# SignalSelector.net
KiCad netlist of a schematic drawn in EAGLE
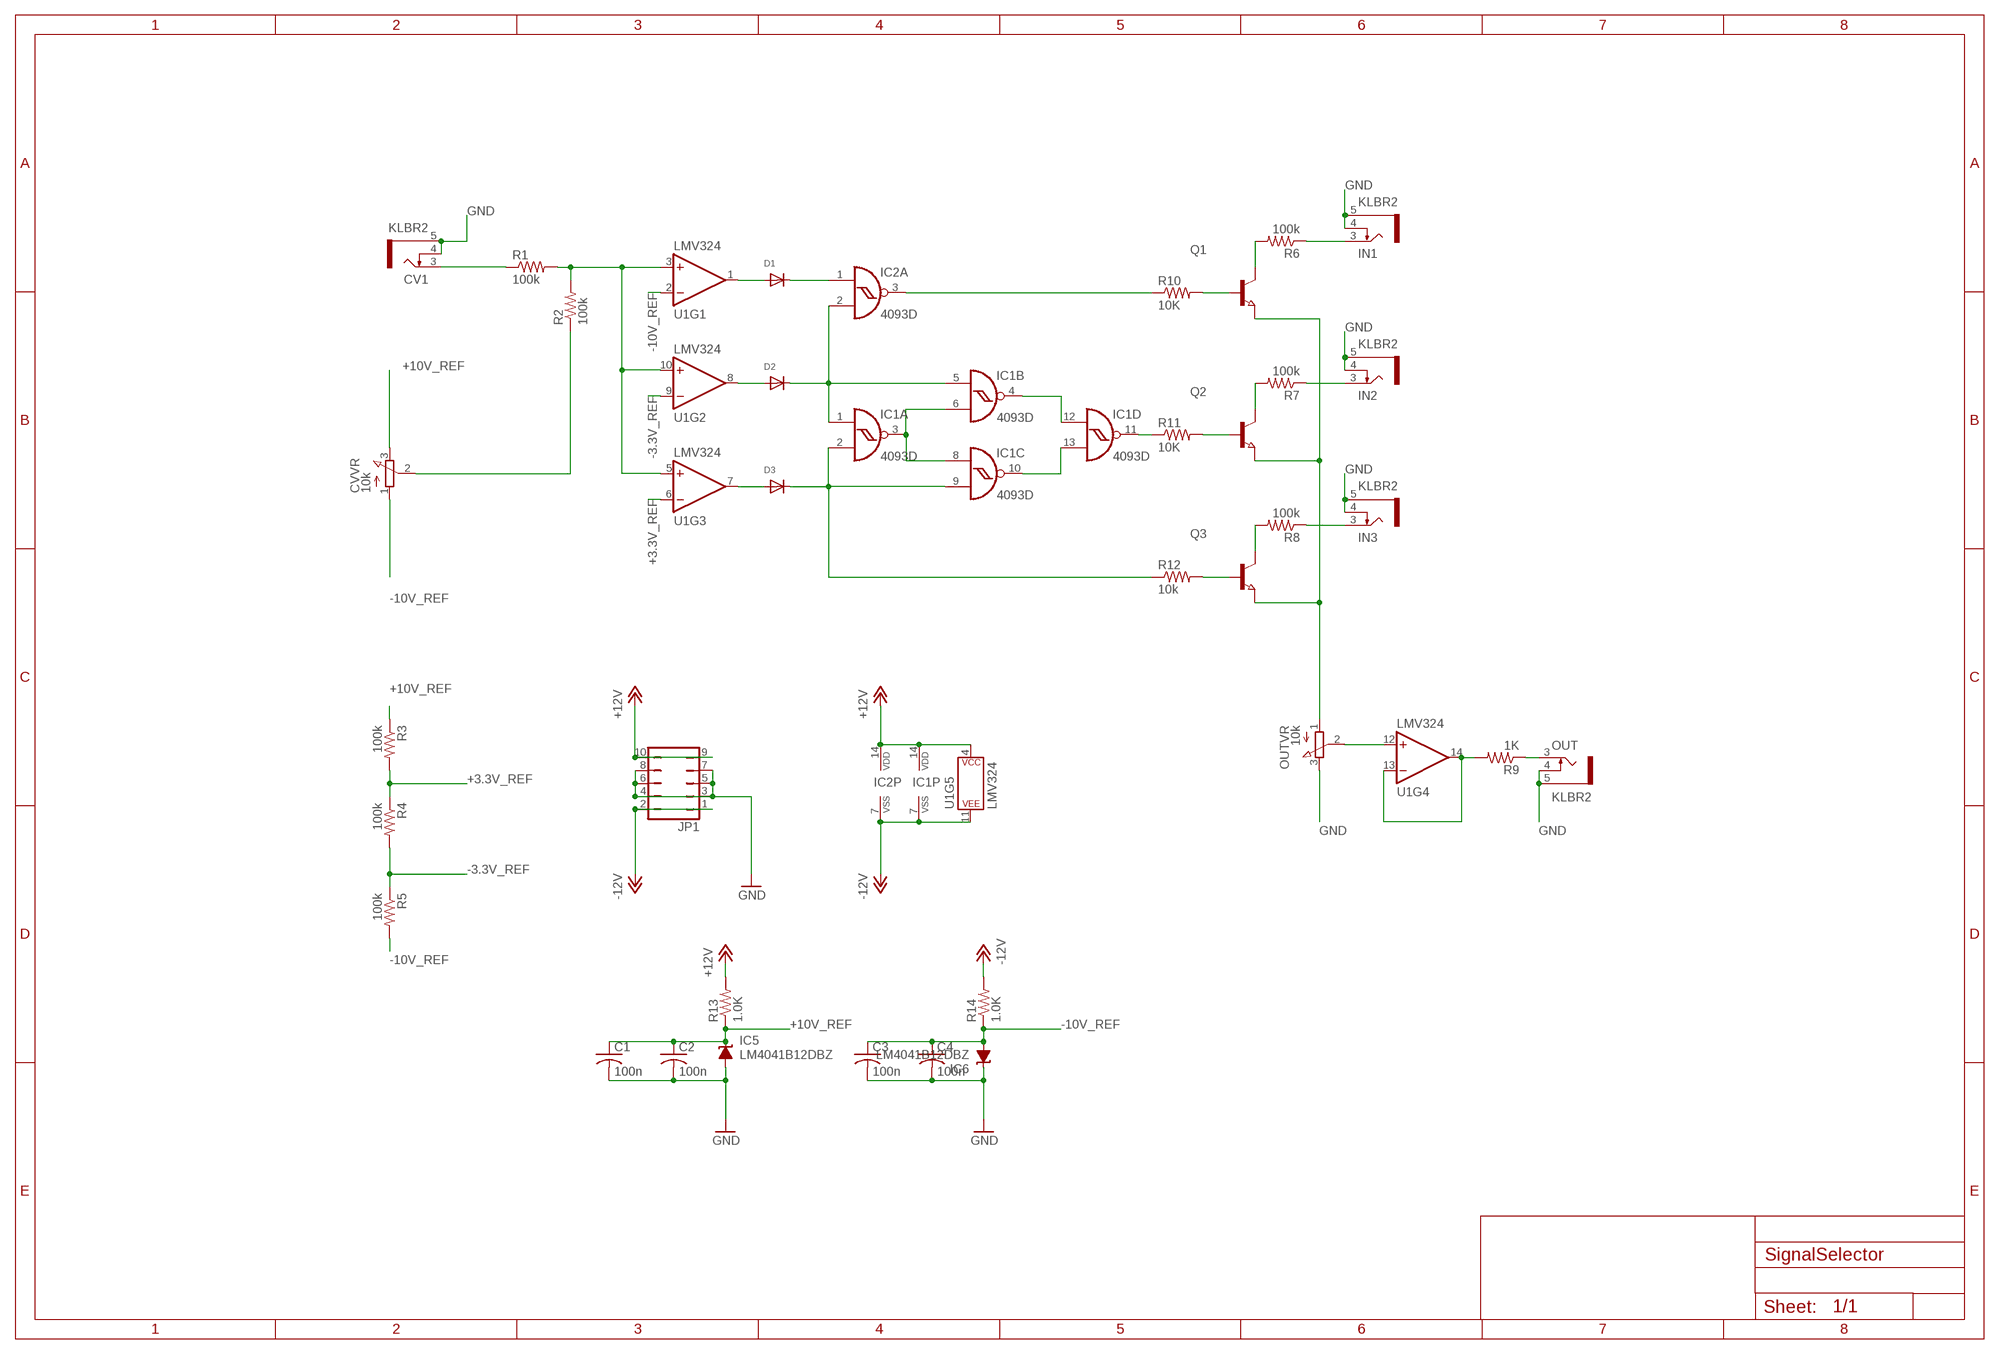
[diagram p0: schematic, sheet 1]

(export (version "E")
  (design (tool "Eeschema 10.0.6"))
  (components
    (comp (ref "C1")
      (value "100n")
      (footprint "eagle-import:C0603")
      (libsource (lib "eagle-import") (part "C-USC0603"))
    )
    (comp (ref "C2")
      (value "100n")
      (footprint "eagle-import:C0603")
      (libsource (lib "eagle-import") (part "C-USC0603"))
    )
    (comp (ref "C3")
      (value "100n")
      (footprint "eagle-import:C0603")
      (libsource (lib "eagle-import") (part "C-USC0603"))
    )
    (comp (ref "C4")
      (value "100n")
      (footprint "eagle-import:C0603")
      (libsource (lib "eagle-import") (part "C-USC0603"))
    )
    (comp (ref "CV1")
      (value "KLBR2")
      (footprint "eagle-import:KLBR2")
      (libsource (lib "eagle-import") (part "KLBR?2"))
    )
    (comp (ref "CVVR")
      (value "10k")
      (footprint "eagle-import:3RP_1610N")
      (libsource (lib "eagle-import") (part "3RP/1610N"))
    )
    (comp (ref "D1")
      (value "DIODE_SOD-123FL")
      (footprint "eagle-import:SOD-123FL")
      (libsource (lib "eagle-import") (part "DIODE_SOD-123FL"))
    )
    (comp (ref "D2")
      (value "DIODE_SOD-123FL")
      (footprint "eagle-import:SOD-123FL")
      (libsource (lib "eagle-import") (part "DIODE_SOD-123FL"))
    )
    (comp (ref "D3")
      (value "DIODE_SOD-123FL")
      (footprint "eagle-import:SOD-123FL")
      (libsource (lib "eagle-import") (part "DIODE_SOD-123FL"))
    )
    (comp (ref "IC1")
      (value "4093D")
      (footprint "eagle-import:SO14")
      (libsource (lib "eagle-import") (part "4093D"))
    )
    (comp (ref "IC2")
      (value "4093D")
      (footprint "eagle-import:SO14")
      (libsource (lib "eagle-import") (part "4093D"))
    )
    (comp (ref "IC5")
      (value "LM4041B12DBZ")
      (footprint "eagle-import:DBZ_R-PDSO-G3")
      (fields (field (name "MPN") "LM4041B12IDBZR"))
      (libsource (lib "eagle-import") (part "LM4041DBZB12"))
    )
    (comp (ref "IC6")
      (value "LM4041B12DBZ")
      (footprint "eagle-import:DBZ_R-PDSO-G3")
      (fields (field (name "MPN") "LM4041B12IDBZR"))
      (libsource (lib "eagle-import") (part "LM4041DBZB12"))
    )
    (comp (ref "IN1")
      (value "KLBR2")
      (footprint "eagle-import:KLBR2")
      (libsource (lib "eagle-import") (part "KLBR?2"))
    )
    (comp (ref "IN2")
      (value "KLBR2")
      (footprint "eagle-import:KLBR2")
      (libsource (lib "eagle-import") (part "KLBR?2"))
    )
    (comp (ref "IN3")
      (value "KLBR2")
      (footprint "eagle-import:KLBR2")
      (libsource (lib "eagle-import") (part "KLBR?2"))
    )
    (comp (ref "JP1")
      (value "JP5Q")
      (footprint "eagle-import:JP5Q")
      (libsource (lib "eagle-import") (part "JP5Q"))
    )
    (comp (ref "OUT")
      (value "KLBR2")
      (footprint "eagle-import:KLBR2")
      (libsource (lib "eagle-import") (part "KLBR?2"))
    )
    (comp (ref "OUTVR")
      (value "10k")
      (footprint "eagle-import:3RP_1610N")
      (libsource (lib "eagle-import") (part "3RP/1610N"))
    )
    (comp (ref "Q1")
      (value "NPN-TRANSISTOR_SOT23")
      (footprint "eagle-import:SOT23")
      (libsource (lib "eagle-import") (part "NPN-TRANSISTOR_SOT23"))
    )
    (comp (ref "Q2")
      (value "NPN-TRANSISTOR_SOT23")
      (footprint "eagle-import:SOT23")
      (libsource (lib "eagle-import") (part "NPN-TRANSISTOR_SOT23"))
    )
    (comp (ref "Q3")
      (value "NPN-TRANSISTOR_SOT23")
      (footprint "eagle-import:SOT23")
      (libsource (lib "eagle-import") (part "NPN-TRANSISTOR_SOT23"))
    )
    (comp (ref "R1")
      (value "100k")
      (footprint "eagle-import:R0603")
      (libsource (lib "eagle-import") (part "R-US_R0603"))
    )
    (comp (ref "R2")
      (value "100k")
      (footprint "eagle-import:R0603")
      (libsource (lib "eagle-import") (part "R-US_R0603"))
    )
    (comp (ref "R3")
      (value "100k")
      (footprint "eagle-import:R0603")
      (libsource (lib "eagle-import") (part "R-US_R0603"))
    )
    (comp (ref "R4")
      (value "100k")
      (footprint "eagle-import:R0603")
      (libsource (lib "eagle-import") (part "R-US_R0603"))
    )
    (comp (ref "R5")
      (value "100k")
      (footprint "eagle-import:R0603")
      (libsource (lib "eagle-import") (part "R-US_R0603"))
    )
    (comp (ref "R6")
      (value "100k")
      (footprint "eagle-import:R0603")
      (libsource (lib "eagle-import") (part "R-US_R0603"))
    )
    (comp (ref "R7")
      (value "100k")
      (footprint "eagle-import:R0603")
      (libsource (lib "eagle-import") (part "R-US_R0603"))
    )
    (comp (ref "R8")
      (value "100k")
      (footprint "eagle-import:R0603")
      (libsource (lib "eagle-import") (part "R-US_R0603"))
    )
    (comp (ref "R9")
      (value "1K")
      (footprint "eagle-import:R0603")
      (libsource (lib "eagle-import") (part "R-US_R0603"))
    )
    (comp (ref "R10")
      (value "10K")
      (footprint "eagle-import:R0603")
      (libsource (lib "eagle-import") (part "R-US_R0603"))
    )
    (comp (ref "R11")
      (value "10K")
      (footprint "eagle-import:R0603")
      (libsource (lib "eagle-import") (part "R-US_R0603"))
    )
    (comp (ref "R12")
      (value "10k")
      (footprint "eagle-import:R0603")
      (libsource (lib "eagle-import") (part "R-US_R0603"))
    )
    (comp (ref "R13")
      (value "1.0K")
      (footprint "eagle-import:R0603")
      (libsource (lib "eagle-import") (part "R-US_R0603"))
    )
    (comp (ref "R14")
      (value "1.0K")
      (footprint "eagle-import:R0603")
      (libsource (lib "eagle-import") (part "R-US_R0603"))
    )
    (comp (ref "U1")
      (value "LMV324")
      (footprint "eagle-import:SO14")
      (libsource (lib "eagle-import") (part "LMV324"))
    )
  )
  (nets
    (net (code "1") (name "+12V") (class "Default")
      (node (ref "IC1") (pin "14") (pinfunction "VDD_14") (pintype "power_in"))
      (node (ref "IC2") (pin "14") (pinfunction "VDD_14") (pintype "power_in"))
      (node (ref "JP1") (pin "10") (pinfunction "10_10") (pintype "passive"))
      (node (ref "JP1") (pin "9") (pinfunction "9_9") (pintype "passive"))
      (node (ref "R13") (pin "2") (pinfunction "2_2") (pintype "passive"))
      (node (ref "U1") (pin "4") (pinfunction "P$V+_4") (pintype "bidirectional"))
    )
    (net (code "2") (name "-12V") (class "Default")
      (node (ref "IC1") (pin "7") (pinfunction "VSS_7") (pintype "power_in"))
      (node (ref "IC2") (pin "7") (pinfunction "VSS_7") (pintype "power_in"))
      (node (ref "JP1") (pin "1") (pinfunction "1_1") (pintype "passive"))
      (node (ref "JP1") (pin "2") (pinfunction "2_2") (pintype "passive"))
      (node (ref "R14") (pin "2") (pinfunction "2_2") (pintype "passive"))
      (node (ref "U1") (pin "11") (pinfunction "P$V-_11") (pintype "bidirectional"))
    )
    (net (code "3") (name "/+3.3V_REF") (class "Default")
      (node (ref "R3") (pin "2") (pinfunction "2_2") (pintype "passive"))
      (node (ref "R4") (pin "1") (pinfunction "1_1") (pintype "passive"))
      (node (ref "U1") (pin "6") (pinfunction "-IN_6") (pintype "input"))
    )
    (net (code "4") (name "/+10V_REF") (class "Default")
      (node (ref "C1") (pin "1") (pinfunction "1_1") (pintype "passive"))
      (node (ref "C2") (pin "1") (pinfunction "1_1") (pintype "passive"))
      (node (ref "CVVR") (pin "3") (pinfunction "E_3") (pintype "passive"))
      (node (ref "IC5") (pin "1") (pinfunction "C_1") (pintype "passive"))
      (node (ref "R13") (pin "1") (pinfunction "1_1") (pintype "passive"))
      (node (ref "R3") (pin "1") (pinfunction "1_1") (pintype "passive"))
    )
    (net (code "5") (name "/-3.3V_REF") (class "Default")
      (node (ref "R4") (pin "2") (pinfunction "2_2") (pintype "passive"))
      (node (ref "R5") (pin "1") (pinfunction "1_1") (pintype "passive"))
      (node (ref "U1") (pin "9") (pinfunction "-IN_9") (pintype "input"))
    )
    (net (code "6") (name "/-10V_REF") (class "Default")
      (node (ref "C3") (pin "1") (pinfunction "1_1") (pintype "passive"))
      (node (ref "C4") (pin "1") (pinfunction "1_1") (pintype "passive"))
      (node (ref "CVVR") (pin "1") (pinfunction "A_1") (pintype "passive"))
      (node (ref "IC6") (pin "2") (pinfunction "A_2") (pintype "passive"))
      (node (ref "R14") (pin "1") (pinfunction "1_1") (pintype "passive"))
      (node (ref "R5") (pin "2") (pinfunction "2_2") (pintype "passive"))
      (node (ref "U1") (pin "2") (pinfunction "-IN_2") (pintype "input"))
    )
    (net (code "7") (name "GND") (class "Default")
      (node (ref "C1") (pin "2") (pinfunction "2_2") (pintype "passive"))
      (node (ref "C2") (pin "2") (pinfunction "2_2") (pintype "passive"))
      (node (ref "C3") (pin "2") (pinfunction "2_2") (pintype "passive"))
      (node (ref "C4") (pin "2") (pinfunction "2_2") (pintype "passive"))
      (node (ref "CV1") (pin "4") (pinfunction "4_4") (pintype "passive"))
      (node (ref "CV1") (pin "5") (pinfunction "5_5") (pintype "passive"))
      (node (ref "IC5") (pin "2") (pinfunction "A_2") (pintype "passive"))
      (node (ref "IC6") (pin "1") (pinfunction "C_1") (pintype "passive"))
      (node (ref "IN1") (pin "4") (pinfunction "4_4") (pintype "passive"))
      (node (ref "IN1") (pin "5") (pinfunction "5_5") (pintype "passive"))
      (node (ref "IN2") (pin "4") (pinfunction "4_4") (pintype "passive"))
      (node (ref "IN2") (pin "5") (pinfunction "5_5") (pintype "passive"))
      (node (ref "IN3") (pin "4") (pinfunction "4_4") (pintype "passive"))
      (node (ref "IN3") (pin "5") (pinfunction "5_5") (pintype "passive"))
      (node (ref "JP1") (pin "3") (pinfunction "3_3") (pintype "passive"))
      (node (ref "JP1") (pin "4") (pinfunction "4_4") (pintype "passive"))
      (node (ref "JP1") (pin "5") (pinfunction "5_5") (pintype "passive"))
      (node (ref "JP1") (pin "6") (pinfunction "6_6") (pintype "passive"))
      (node (ref "JP1") (pin "7") (pinfunction "7_7") (pintype "passive"))
      (node (ref "JP1") (pin "8") (pinfunction "8_8") (pintype "passive"))
      (node (ref "OUT") (pin "4") (pinfunction "4_4") (pintype "passive"))
      (node (ref "OUT") (pin "5") (pinfunction "5_5") (pintype "passive"))
      (node (ref "OUTVR") (pin "3") (pinfunction "E_3") (pintype "passive"))
    )
    (net (code "8") (name "Net-(CV1-Pad3)") (class "Default")
      (node (ref "CV1") (pin "3") (pinfunction "3_3") (pintype "passive"))
      (node (ref "R1") (pin "1") (pinfunction "1_1") (pintype "passive"))
    )
    (net (code "9") (name "Net-(CVVR-S)") (class "Default")
      (node (ref "CVVR") (pin "2") (pinfunction "S_2") (pintype "passive"))
      (node (ref "R2") (pin "1") (pinfunction "1_1") (pintype "passive"))
    )
    (net (code "10") (name "Net-(IC1A-I0)") (class "Default")
      (node (ref "D2") (pin "C") (pinfunction "C_C") (pintype "passive"))
      (node (ref "IC1") (pin "1") (pinfunction "I0_1") (pintype "input"))
      (node (ref "IC1") (pin "5") (pinfunction "I0_5") (pintype "input"))
      (node (ref "IC2") (pin "2") (pinfunction "I1_2") (pintype "input"))
    )
    (net (code "11") (name "Net-(IC1A-I1)") (class "Default")
      (node (ref "D3") (pin "C") (pinfunction "C_C") (pintype "passive"))
      (node (ref "IC1") (pin "2") (pinfunction "I1_2") (pintype "input"))
      (node (ref "IC1") (pin "9") (pinfunction "I1_9") (pintype "input"))
      (node (ref "R12") (pin "1") (pinfunction "1_1") (pintype "passive"))
    )
    (net (code "12") (name "Net-(IC1A-O)") (class "Default")
      (node (ref "IC1") (pin "3") (pinfunction "O_3") (pintype "output"))
      (node (ref "IC1") (pin "6") (pinfunction "I1_6") (pintype "input"))
      (node (ref "IC1") (pin "8") (pinfunction "I0_8") (pintype "input"))
    )
    (net (code "13") (name "Net-(IC1B-O)") (class "Default")
      (node (ref "IC1") (pin "12") (pinfunction "I0_12") (pintype "input"))
      (node (ref "IC1") (pin "4") (pinfunction "O_4") (pintype "output"))
    )
    (net (code "14") (name "Net-(IC1C-O)") (class "Default")
      (node (ref "IC1") (pin "10") (pinfunction "O_10") (pintype "output"))
      (node (ref "IC1") (pin "13") (pinfunction "I1_13") (pintype "input"))
    )
    (net (code "15") (name "Net-(IC1D-O)") (class "Default")
      (node (ref "IC1") (pin "11") (pinfunction "O_11") (pintype "output"))
      (node (ref "R11") (pin "1") (pinfunction "1_1") (pintype "passive"))
    )
    (net (code "16") (name "Net-(IC2A-I0)") (class "Default")
      (node (ref "D1") (pin "C") (pinfunction "C_C") (pintype "passive"))
      (node (ref "IC2") (pin "1") (pinfunction "I0_1") (pintype "input"))
    )
    (net (code "17") (name "Net-(IC2A-O)") (class "Default")
      (node (ref "IC2") (pin "3") (pinfunction "O_3") (pintype "output"))
      (node (ref "R10") (pin "1") (pinfunction "1_1") (pintype "passive"))
    )
    (net (code "18") (name "Net-(IN1-Pad3)") (class "Default")
      (node (ref "IN1") (pin "3") (pinfunction "3_3") (pintype "passive"))
      (node (ref "R6") (pin "1") (pinfunction "1_1") (pintype "passive"))
    )
    (net (code "19") (name "Net-(IN2-Pad3)") (class "Default")
      (node (ref "IN2") (pin "3") (pinfunction "3_3") (pintype "passive"))
      (node (ref "R7") (pin "1") (pinfunction "1_1") (pintype "passive"))
    )
    (net (code "20") (name "Net-(IN3-Pad3)") (class "Default")
      (node (ref "IN3") (pin "3") (pinfunction "3_3") (pintype "passive"))
      (node (ref "R8") (pin "1") (pinfunction "1_1") (pintype "passive"))
    )
    (net (code "21") (name "Net-(OUT-Pad3)") (class "Default")
      (node (ref "OUT") (pin "3") (pinfunction "3_3") (pintype "passive"))
      (node (ref "R9") (pin "1") (pinfunction "1_1") (pintype "passive"))
    )
    (net (code "22") (name "Net-(OUTVR-A)") (class "Default")
      (node (ref "OUTVR") (pin "1") (pinfunction "A_1") (pintype "passive"))
      (node (ref "Q1") (pin "2") (pinfunction "E_2") (pintype "passive"))
      (node (ref "Q2") (pin "2") (pinfunction "E_2") (pintype "passive"))
      (node (ref "Q3") (pin "2") (pinfunction "E_2") (pintype "passive"))
    )
    (net (code "23") (name "Net-(OUTVR-S)") (class "Default")
      (node (ref "OUTVR") (pin "2") (pinfunction "S_2") (pintype "passive"))
      (node (ref "U1") (pin "12") (pinfunction "+IN_12") (pintype "input"))
    )
    (net (code "24") (name "Net-(Q1-B)") (class "Default")
      (node (ref "Q1") (pin "1") (pinfunction "B_1") (pintype "passive"))
      (node (ref "R10") (pin "2") (pinfunction "2_2") (pintype "passive"))
    )
    (net (code "25") (name "Net-(Q1-C)") (class "Default")
      (node (ref "Q1") (pin "3") (pinfunction "C_3") (pintype "passive"))
      (node (ref "R6") (pin "2") (pinfunction "2_2") (pintype "passive"))
    )
    (net (code "26") (name "Net-(Q2-B)") (class "Default")
      (node (ref "Q2") (pin "1") (pinfunction "B_1") (pintype "passive"))
      (node (ref "R11") (pin "2") (pinfunction "2_2") (pintype "passive"))
    )
    (net (code "27") (name "Net-(Q2-C)") (class "Default")
      (node (ref "Q2") (pin "3") (pinfunction "C_3") (pintype "passive"))
      (node (ref "R7") (pin "2") (pinfunction "2_2") (pintype "passive"))
    )
    (net (code "28") (name "Net-(Q3-B)") (class "Default")
      (node (ref "Q3") (pin "1") (pinfunction "B_1") (pintype "passive"))
      (node (ref "R12") (pin "2") (pinfunction "2_2") (pintype "passive"))
    )
    (net (code "29") (name "Net-(Q3-C)") (class "Default")
      (node (ref "Q3") (pin "3") (pinfunction "C_3") (pintype "passive"))
      (node (ref "R8") (pin "2") (pinfunction "2_2") (pintype "passive"))
    )
    (net (code "30") (name "Net-(U1A-+IN)") (class "Default")
      (node (ref "R1") (pin "2") (pinfunction "2_2") (pintype "passive"))
      (node (ref "R2") (pin "2") (pinfunction "2_2") (pintype "passive"))
      (node (ref "U1") (pin "10") (pinfunction "+IN_10") (pintype "input"))
      (node (ref "U1") (pin "3") (pinfunction "+IN_3") (pintype "input"))
      (node (ref "U1") (pin "5") (pinfunction "+IN_5") (pintype "input"))
    )
    (net (code "31") (name "Net-(U1A-OUT)") (class "Default")
      (node (ref "D1") (pin "A") (pinfunction "A_A") (pintype "passive"))
      (node (ref "U1") (pin "1") (pinfunction "OUT_1") (pintype "output"))
    )
    (net (code "32") (name "Net-(U1B-OUT)") (class "Default")
      (node (ref "D2") (pin "A") (pinfunction "A_A") (pintype "passive"))
      (node (ref "U1") (pin "8") (pinfunction "OUT_8") (pintype "output"))
    )
    (net (code "33") (name "Net-(U1C-OUT)") (class "Default")
      (node (ref "D3") (pin "A") (pinfunction "A_A") (pintype "passive"))
      (node (ref "U1") (pin "7") (pinfunction "OUT_7") (pintype "output"))
    )
    (net (code "34") (name "Net-(U1D--IN)") (class "Default")
      (node (ref "R9") (pin "2") (pinfunction "2_2") (pintype "passive"))
      (node (ref "U1") (pin "13") (pinfunction "-IN_13") (pintype "input"))
      (node (ref "U1") (pin "14") (pinfunction "OUT_14") (pintype "output"))
    )
  )
)
